# Main.net
KiCad netlist of a schematic drawn in Altium Designer
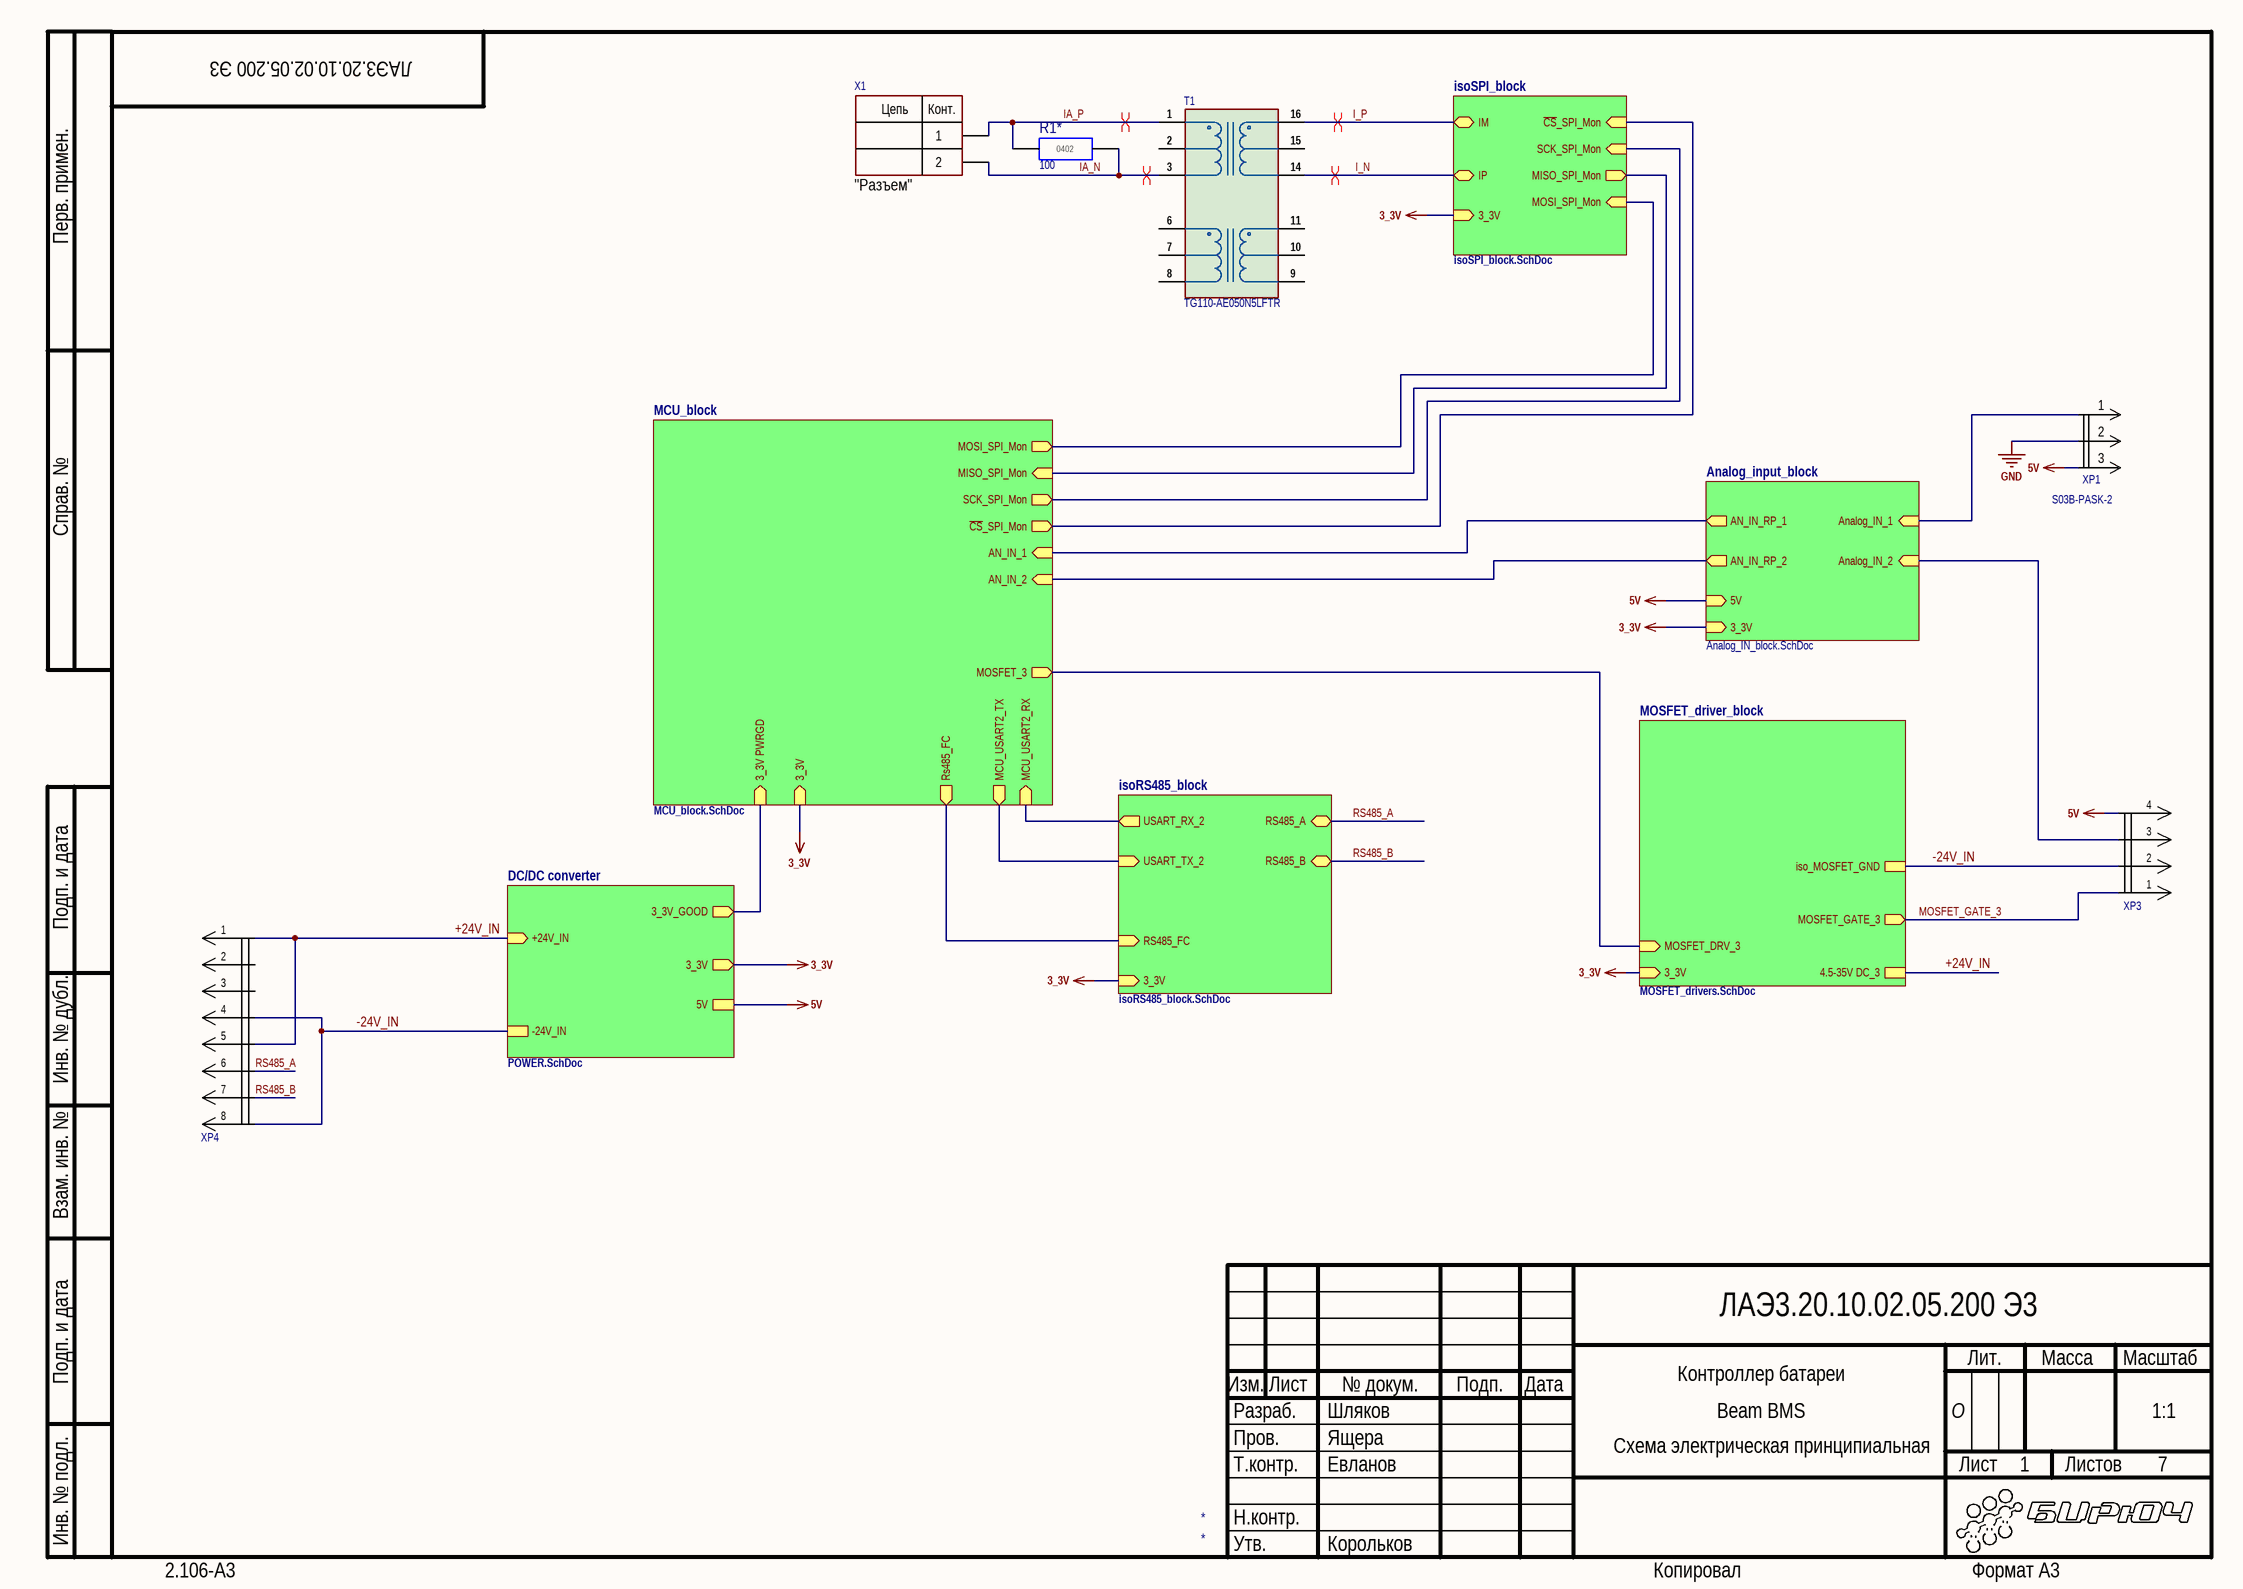
[diagram p0: Main.SchDoc]

(export (version "E")
  (design (tool "Eeschema 10.0.6"))
  (components
    (comp (ref "R1*")
      (value "100")
      (footprint "CR0402(1005)")
      (description "Чип резистор")
      (fields (field (name "TOLERANCE") "5%") (field (name "Comment") "CR0402-100-±5%"))
      (libsource (lib "Чип резисторы_small") (part "CR0402-#-±5%"))
    )
    (comp (ref "T1")
      (value "TG110-AE050N5LFTR")
      (footprint "SMT4_SOIC16_N5")
      (fields (field (name "MP") "TG110-AE050N5LFTR"))
      (libsource (lib "batmon_ICs") (part "TG110-AE050N5LFTR"))
    )
    (comp (ref "X1")
      (value "~")
      (footprint "MOLEX 1053131102")
      (fields
        (field (name "MANUFACTURER") "Molex")
        (field (name "VALUEMANUFACTURERPARTNUMBER") "Connector, 2pin, 2.5mm, 1500VDC, 6.5A")
        (field (name "PARTNUMBER") "1053131102")
        (field (name "COMMENTTEXT") "\"Разъем\"")
      )
      (libsource (lib "batmon_ICs") (part "Molex 1053131102"))
    )
    (comp (ref "XP1")
      (value "S03B-PASK-2")
      (footprint "S03B-PASK-2")
      (description "Вилка угловая выводная, шаг 2мм")
      (libsource (lib "batmon_ICs") (part "S03B-PASK-2"))
    )
    (comp (ref "XP3")
      (value "1565749-3")
      (footprint "TE_1565749-3")
      (fields (field (name "MANUFACTURER") "TE Connectivity"))
      (libsource (lib "batmon_ICs") (part "TE-1565749-3"))
    )
    (comp (ref "XP4")
      (value "1-1379684-1")
      (footprint "TE_1379684-1")
      (fields (field (name "MANUFACTURER") "TE Connectivity"))
      (libsource (lib "batmon_ICs") (part "TE-1379684-1"))
    )
  )
  (nets
    (net (code "1") (name "/+24V_IN") (class "Default")
      (node (ref "XP4") (pin "1") (pinfunction "1_1") (pintype "passive"))
      (node (ref "XP4") (pin "5") (pinfunction "5_5") (pintype "passive"))
    )
    (net (code "2") (name "/-24V_IN") (class "Default")
      (node (ref "XP3") (pin "2") (pinfunction "2_2") (pintype "passive"))
      (node (ref "XP4") (pin "4") (pinfunction "4_4") (pintype "passive"))
      (node (ref "XP4") (pin "8") (pinfunction "8_8") (pintype "passive"))
    )
    (net (code "6") (name "/Analog_IN_1") (class "Default")
      (node (ref "XP1") (pin "1") (pinfunction "1_1") (pintype "passive"))
    )
    (net (code "7") (name "/Analog_IN_2") (class "Default")
      (node (ref "XP3") (pin "3") (pinfunction "3_3") (pintype "passive"))
    )
    (net (code "8") (name "/IA_N") (class "Default")
      (node (ref "R1*") (pin "2") (pinfunction "-_2") (pintype "passive"))
      (node (ref "T1") (pin "3") (pinfunction "P1_2_3") (pintype "passive"))
      (node (ref "X1") (pin "2") (pinfunction "2_2") (pintype "passive"))
    )
    (net (code "9") (name "/IA_P") (class "Default")
      (node (ref "R1*") (pin "1") (pinfunction "+_1") (pintype "passive"))
      (node (ref "T1") (pin "1") (pinfunction "P1_1_1") (pintype "passive"))
      (node (ref "X1") (pin "1") (pinfunction "1_1") (pintype "passive"))
    )
    (net (code "10") (name "/I_N") (class "Default")
      (node (ref "T1") (pin "14") (pinfunction "S1_P_14") (pintype "passive"))
    )
    (net (code "11") (name "/I_P") (class "Default")
      (node (ref "T1") (pin "16") (pinfunction "S1_N_16") (pintype "passive"))
    )
    (net (code "15") (name "/MOSFET_GATE_3") (class "Default")
      (node (ref "XP3") (pin "1") (pinfunction "1_1") (pintype "passive"))
    )
    (net (code "17") (name "/RS485_A") (class "Default")
      (node (ref "XP4") (pin "6") (pinfunction "6_6") (pintype "passive"))
    )
    (net (code "18") (name "/RS485_B") (class "Default")
      (node (ref "XP4") (pin "7") (pinfunction "7_7") (pintype "passive"))
    )
    (net (code "24") (name "5V") (class "Default")
      (node (ref "XP1") (pin "3") (pinfunction "3_3") (pintype "passive"))
      (node (ref "XP3") (pin "4") (pinfunction "4_4") (pintype "passive"))
    )
    (net (code "25") (name "GND") (class "Default")
      (node (ref "XP1") (pin "2") (pinfunction "2_2") (pintype "passive"))
    )
    (net (code "26") (name "unconnected-(T1-NC@1-Pad4)") (class "Default")
      (node (ref "T1") (pin "4") (pinfunction "NC@1_4") (pintype "passive"))
    )
    (net (code "27") (name "unconnected-(T1-NC@2-Pad5)") (class "Default")
      (node (ref "T1") (pin "5") (pinfunction "NC@2_5") (pintype "passive"))
    )
    (net (code "28") (name "unconnected-(T1-NC@3-Pad13)") (class "Default")
      (node (ref "T1") (pin "13") (pinfunction "NC@3_13") (pintype "passive"))
    )
    (net (code "29") (name "unconnected-(T1-NC@4-Pad12)") (class "Default")
      (node (ref "T1") (pin "12") (pinfunction "NC@4_12") (pintype "passive"))
    )
    (net (code "30") (name "unconnected-(T1-P1_T-Pad2)") (class "Default")
      (node (ref "T1") (pin "2") (pinfunction "P1_T_2") (pintype "passive"))
    )
    (net (code "31") (name "unconnected-(T1-P2_1-Pad6)") (class "Default")
      (node (ref "T1") (pin "6") (pinfunction "P2_1_6") (pintype "passive"))
    )
    (net (code "32") (name "unconnected-(T1-P2_2-Pad8)") (class "Default")
      (node (ref "T1") (pin "8") (pinfunction "P2_2_8") (pintype "passive"))
    )
    (net (code "33") (name "unconnected-(T1-P2_T-Pad7)") (class "Default")
      (node (ref "T1") (pin "7") (pinfunction "P2_T_7") (pintype "passive"))
    )
    (net (code "34") (name "unconnected-(T1-S1_T-Pad15)") (class "Default")
      (node (ref "T1") (pin "15") (pinfunction "S1_T_15") (pintype "passive"))
    )
    (net (code "35") (name "unconnected-(T1-S2_N-Pad11)") (class "Default")
      (node (ref "T1") (pin "11") (pinfunction "S2_N_11") (pintype "passive"))
    )
    (net (code "36") (name "unconnected-(T1-S2_P-Pad9)") (class "Default")
      (node (ref "T1") (pin "9") (pinfunction "S2_P_9") (pintype "passive"))
    )
    (net (code "37") (name "unconnected-(T1-S2_T-Pad10)") (class "Default")
      (node (ref "T1") (pin "10") (pinfunction "S2_T_10") (pintype "passive"))
    )
    (net (code "38") (name "unconnected-(XP4-Pad2)") (class "Default")
      (node (ref "XP4") (pin "2") (pinfunction "2_2") (pintype "passive"))
    )
    (net (code "39") (name "unconnected-(XP4-Pad3)") (class "Default")
      (node (ref "XP4") (pin "3") (pinfunction "3_3") (pintype "passive"))
    )
  )
)
